# combo.net
KiCad netlist of a schematic drawn in EAGLE
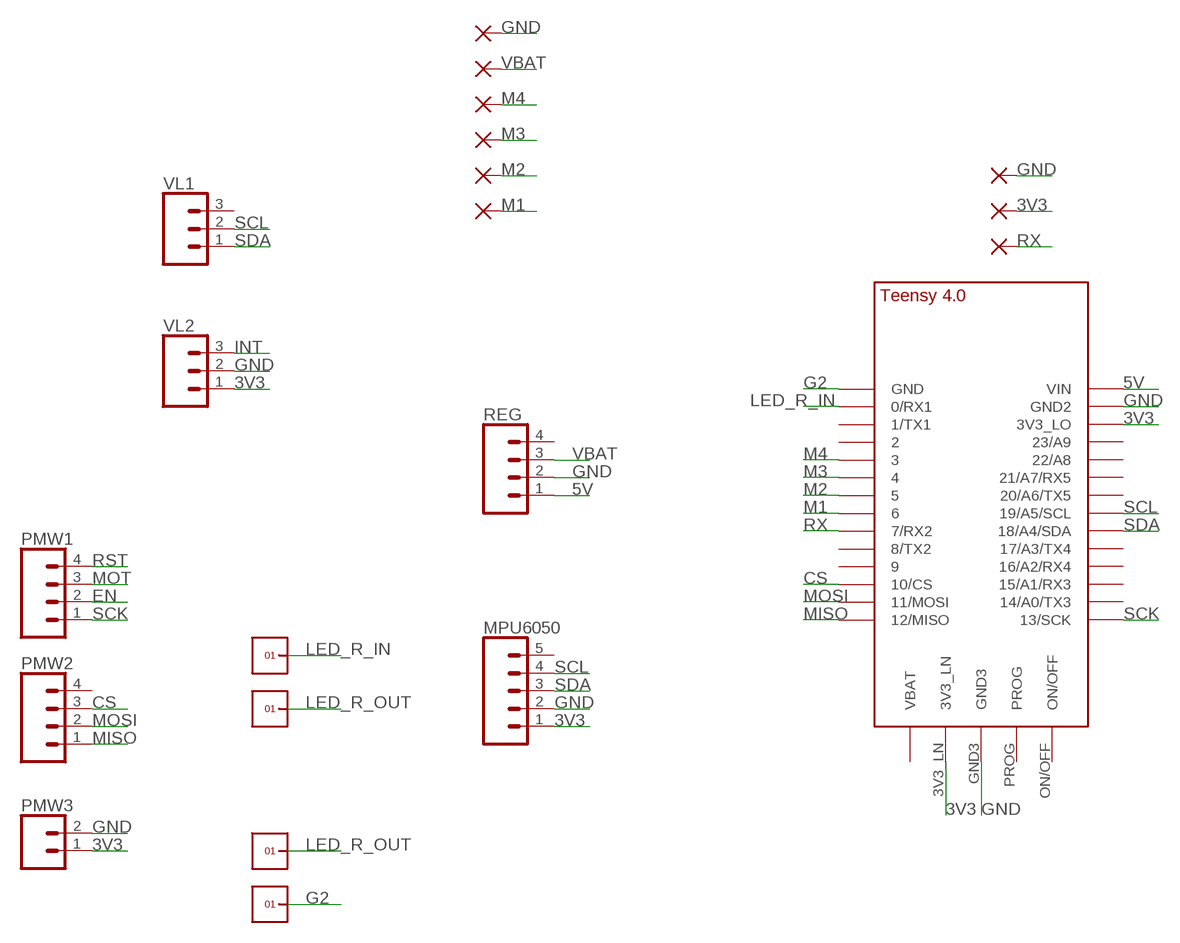
[diagram p0: schematic, sheet 1]

(export (version "E")
  (design (tool "Eeschema 10.0.6"))
  (components
    (comp (ref "3V")
      (value "SMD2")
      (footprint "eagle-import:SMD1,27-2,54")
      (libsource (lib "eagle-import") (part "SMD2"))
    )
    (comp (ref "GD")
      (value "SMD2")
      (footprint "eagle-import:SMD1,27-2,54")
      (libsource (lib "eagle-import") (part "SMD2"))
    )
    (comp (ref "GND")
      (value "SMD2")
      (footprint "eagle-import:SMD1,27-2,54")
      (libsource (lib "eagle-import") (part "SMD2"))
    )
    (comp (ref "M1")
      (value "SMD2")
      (footprint "eagle-import:SMD1,27-2,54")
      (libsource (lib "eagle-import") (part "SMD2"))
    )
    (comp (ref "M2")
      (value "SMD2")
      (footprint "eagle-import:SMD1,27-2,54")
      (libsource (lib "eagle-import") (part "SMD2"))
    )
    (comp (ref "M3")
      (value "SMD2")
      (footprint "eagle-import:SMD1,27-2,54")
      (libsource (lib "eagle-import") (part "SMD2"))
    )
    (comp (ref "M4")
      (value "SMD2")
      (footprint "eagle-import:SMD1,27-2,54")
      (libsource (lib "eagle-import") (part "SMD2"))
    )
    (comp (ref "MPU6050")
      (value "CONN_05NO_SILK")
      (footprint "eagle-import:1X05_NO_SILK")
      (libsource (lib "eagle-import") (part "CONN_05NO_SILK"))
    )
    (comp (ref "PMW1")
      (value "CONN_041X04_NO_SILK")
      (footprint "eagle-import:1X04_NO_SILK")
      (libsource (lib "eagle-import") (part "CONN_041X04_NO_SILK"))
    )
    (comp (ref "PMW2")
      (value "CONN_041X04_NO_SILK")
      (footprint "eagle-import:1X04_NO_SILK")
      (libsource (lib "eagle-import") (part "CONN_041X04_NO_SILK"))
    )
    (comp (ref "PMW3")
      (value "CONN_021X02_NO_SILK")
      (footprint "eagle-import:1X02_NO_SILK")
      (libsource (lib "eagle-import") (part "CONN_021X02_NO_SILK"))
    )
    (comp (ref "REG")
      (value "CONN_041X04_NO_SILK")
      (footprint "eagle-import:1X04_NO_SILK")
      (libsource (lib "eagle-import") (part "CONN_041X04_NO_SILK"))
    )
    (comp (ref "RX")
      (value "SMD2")
      (footprint "eagle-import:SMD1,27-2,54")
      (libsource (lib "eagle-import") (part "SMD2"))
    )
    (comp (ref "U$1")
      (value "TEENSY_4.0")
      (footprint "eagle-import:TEENSY_4.0")
      (libsource (lib "eagle-import") (part "TEENSY_4.0"))
    )
    (comp (ref "U$3")
      (value "1X1")
      (footprint "eagle-import:1X1")
      (libsource (lib "eagle-import") (part "1X1"))
    )
    (comp (ref "U$4")
      (value "1X1")
      (footprint "eagle-import:1X1")
      (libsource (lib "eagle-import") (part "1X1"))
    )
    (comp (ref "U$6")
      (value "1X1")
      (footprint "eagle-import:1X1")
      (libsource (lib "eagle-import") (part "1X1"))
    )
    (comp (ref "U$7")
      (value "1X1")
      (footprint "eagle-import:1X1")
      (libsource (lib "eagle-import") (part "1X1"))
    )
    (comp (ref "VBAT")
      (value "SMD2")
      (footprint "eagle-import:SMD1,27-2,54")
      (libsource (lib "eagle-import") (part "SMD2"))
    )
    (comp (ref "VL1")
      (value "CONN_031X03_NO_SILK")
      (footprint "eagle-import:1X03_NO_SILK")
      (libsource (lib "eagle-import") (part "CONN_031X03_NO_SILK"))
    )
    (comp (ref "VL2")
      (value "CONN_031X03_NO_SILK")
      (footprint "eagle-import:1X03_NO_SILK")
      (libsource (lib "eagle-import") (part "CONN_031X03_NO_SILK"))
    )
  )
  (nets
    (net (code "1") (name "/3V3") (class "Default")
      (node (ref "3V") (pin "1") (pinfunction "P_1") (pintype "passive"))
      (node (ref "MPU6050") (pin "1") (pinfunction "1_1") (pintype "passive"))
      (node (ref "PMW3") (pin "1") (pinfunction "1_1") (pintype "passive"))
      (node (ref "U$1") (pin "3V3_LN") (pinfunction "3V3_LN_3V3_LN") (pintype "bidirectional"))
      (node (ref "U$1") (pin "3V3_LO") (pinfunction "3V3_LO_3V3_LO") (pintype "bidirectional"))
      (node (ref "VL2") (pin "1") (pinfunction "1_1") (pintype "passive"))
    )
    (net (code "2") (name "/5V") (class "Default")
      (node (ref "REG") (pin "1") (pinfunction "1_1") (pintype "passive"))
      (node (ref "U$1") (pin "VIN") (pinfunction "VIN_VIN") (pintype "bidirectional"))
    )
    (net (code "3") (name "/CS") (class "Default")
      (node (ref "PMW2") (pin "3") (pinfunction "3_3") (pintype "passive"))
      (node (ref "U$1") (pin "10/CS") (pinfunction "10/CS_10/CS") (pintype "bidirectional"))
    )
    (net (code "4") (name "/EN") (class "Default")
      (node (ref "PMW1") (pin "2") (pinfunction "2_2") (pintype "passive"))
    )
    (net (code "5") (name "/G2") (class "Default")
      (node (ref "U$1") (pin "GND") (pinfunction "GND_GND") (pintype "bidirectional"))
      (node (ref "U$7") (pin "1") (pinfunction "1_1") (pintype "bidirectional"))
    )
    (net (code "6") (name "/GND") (class "Default")
      (node (ref "GD") (pin "1") (pinfunction "P_1") (pintype "passive"))
      (node (ref "GND") (pin "1") (pinfunction "P_1") (pintype "passive"))
      (node (ref "MPU6050") (pin "2") (pinfunction "2_2") (pintype "passive"))
      (node (ref "PMW3") (pin "2") (pinfunction "2_2") (pintype "passive"))
      (node (ref "REG") (pin "2") (pinfunction "2_2") (pintype "passive"))
      (node (ref "U$1") (pin "GND2") (pinfunction "GND2_GND2") (pintype "bidirectional"))
      (node (ref "U$1") (pin "GND3") (pinfunction "GND3_GND3") (pintype "bidirectional"))
      (node (ref "VL2") (pin "2") (pinfunction "2_2") (pintype "passive"))
    )
    (net (code "7") (name "/INT") (class "Default")
      (node (ref "VL2") (pin "3") (pinfunction "3_3") (pintype "passive"))
    )
    (net (code "8") (name "/LED_R_IN") (class "Default")
      (node (ref "U$1") (pin "0/RX") (pinfunction "0/RX1_0/RX") (pintype "bidirectional"))
      (node (ref "U$3") (pin "1") (pinfunction "1_1") (pintype "bidirectional"))
    )
    (net (code "9") (name "/LED_R_OUT") (class "Default")
      (node (ref "U$4") (pin "1") (pinfunction "1_1") (pintype "bidirectional"))
      (node (ref "U$6") (pin "1") (pinfunction "1_1") (pintype "bidirectional"))
    )
    (net (code "10") (name "/M1") (class "Default")
      (node (ref "M1") (pin "1") (pinfunction "P_1") (pintype "passive"))
      (node (ref "U$1") (pin "6") (pinfunction "6_6") (pintype "bidirectional"))
    )
    (net (code "11") (name "/M2") (class "Default")
      (node (ref "M2") (pin "1") (pinfunction "P_1") (pintype "passive"))
      (node (ref "U$1") (pin "5") (pinfunction "5_5") (pintype "bidirectional"))
    )
    (net (code "12") (name "/M3") (class "Default")
      (node (ref "M3") (pin "1") (pinfunction "P_1") (pintype "passive"))
      (node (ref "U$1") (pin "4/CANRX") (pinfunction "4_4/CANRX") (pintype "bidirectional"))
    )
    (net (code "13") (name "/M4") (class "Default")
      (node (ref "M4") (pin "1") (pinfunction "P_1") (pintype "passive"))
      (node (ref "U$1") (pin "3/CANTX") (pinfunction "3_3/CANTX") (pintype "bidirectional"))
    )
    (net (code "14") (name "/MISO") (class "Default")
      (node (ref "PMW2") (pin "1") (pinfunction "1_1") (pintype "passive"))
      (node (ref "U$1") (pin "12/MISO") (pinfunction "12/MISO_12/MISO") (pintype "bidirectional"))
    )
    (net (code "15") (name "/MOSI") (class "Default")
      (node (ref "PMW2") (pin "2") (pinfunction "2_2") (pintype "passive"))
      (node (ref "U$1") (pin "11/MOSI") (pinfunction "11/MOSI_11/MOSI") (pintype "bidirectional"))
    )
    (net (code "16") (name "/MOT") (class "Default")
      (node (ref "PMW1") (pin "3") (pinfunction "3_3") (pintype "passive"))
    )
    (net (code "17") (name "/RST") (class "Default")
      (node (ref "PMW1") (pin "4") (pinfunction "4_4") (pintype "passive"))
    )
    (net (code "18") (name "/RX") (class "Default")
      (node (ref "RX") (pin "1") (pinfunction "P_1") (pintype "passive"))
      (node (ref "U$1") (pin "7") (pinfunction "7/RX2_7") (pintype "bidirectional"))
    )
    (net (code "19") (name "/SCK") (class "Default")
      (node (ref "PMW1") (pin "1") (pinfunction "1_1") (pintype "passive"))
      (node (ref "U$1") (pin "13/SCK") (pinfunction "13/SCK_13/SCK") (pintype "bidirectional"))
    )
    (net (code "20") (name "/SCL") (class "Default")
      (node (ref "MPU6050") (pin "4") (pinfunction "4_4") (pintype "passive"))
      (node (ref "U$1") (pin "19/A5/SCL") (pinfunction "19/A5/SCL_19/A5/SCL") (pintype "bidirectional"))
      (node (ref "VL1") (pin "2") (pinfunction "2_2") (pintype "passive"))
    )
    (net (code "21") (name "/SDA") (class "Default")
      (node (ref "MPU6050") (pin "3") (pinfunction "3_3") (pintype "passive"))
      (node (ref "U$1") (pin "18/A4/SDA") (pinfunction "18/A4/SDA_18/A4/SDA") (pintype "bidirectional"))
      (node (ref "VL1") (pin "1") (pinfunction "1_1") (pintype "passive"))
    )
    (net (code "22") (name "/VBAT") (class "Default")
      (node (ref "REG") (pin "3") (pinfunction "3_3") (pintype "passive"))
      (node (ref "VBAT") (pin "1") (pinfunction "P_1") (pintype "passive"))
    )
    (net (code "23") (name "unconnected-(MPU6050-Pad5)") (class "Default")
      (node (ref "MPU6050") (pin "5") (pinfunction "5_5") (pintype "passive"))
    )
    (net (code "24") (name "unconnected-(PMW2-Pad4)") (class "Default")
      (node (ref "PMW2") (pin "4") (pinfunction "4_4") (pintype "passive"))
    )
    (net (code "25") (name "unconnected-(REG-Pad4)") (class "Default")
      (node (ref "REG") (pin "4") (pinfunction "4_4") (pintype "passive"))
    )
    (net (code "26") (name "unconnected-(U$1-1{slash}TX1-Pad1{slash}TX)") (class "Default")
      (node (ref "U$1") (pin "1/TX") (pinfunction "1/TX1_1/TX") (pintype "bidirectional"))
    )
    (net (code "27") (name "unconnected-(U$1-8{slash}TX2-Pad8)") (class "Default")
      (node (ref "U$1") (pin "8") (pinfunction "8/TX2_8") (pintype "bidirectional"))
    )
    (net (code "28") (name "unconnected-(U$1-9-Pad9{slash}CS)") (class "Default")
      (node (ref "U$1") (pin "9/CS") (pinfunction "9_9/CS") (pintype "bidirectional"))
    )
    (net (code "29") (name "unconnected-(U$1-14{slash}A0{slash}TX3-Pad14{slash}A0)") (class "Default")
      (node (ref "U$1") (pin "14/A0") (pinfunction "14/A0/TX3_14/A0") (pintype "bidirectional"))
    )
    (net (code "30") (name "unconnected-(U$1-15{slash}A1{slash}RX3-Pad15{slash}A1)") (class "Default")
      (node (ref "U$1") (pin "15/A1") (pinfunction "15/A1/RX3_15/A1") (pintype "bidirectional"))
    )
    (net (code "31") (name "unconnected-(U$1-16{slash}A2{slash}RX4-Pad16{slash}A2)") (class "Default")
      (node (ref "U$1") (pin "16/A2") (pinfunction "16/A2/RX4_16/A2") (pintype "bidirectional"))
    )
    (net (code "32") (name "unconnected-(U$1-17{slash}A3{slash}TX4-Pad17{slash}A3)") (class "Default")
      (node (ref "U$1") (pin "17/A3") (pinfunction "17/A3/TX4_17/A3") (pintype "bidirectional"))
    )
    (net (code "33") (name "unconnected-(U$1-20{slash}A6{slash}TX5-Pad20{slash}A6)") (class "Default")
      (node (ref "U$1") (pin "20/A6") (pinfunction "20/A6/TX5_20/A6") (pintype "bidirectional"))
    )
    (net (code "34") (name "unconnected-(U$1-21{slash}A7{slash}RX5-Pad21{slash}A7)") (class "Default")
      (node (ref "U$1") (pin "21/A7") (pinfunction "21/A7/RX5_21/A7") (pintype "bidirectional"))
    )
    (net (code "35") (name "unconnected-(U$1-Pad2)") (class "Default")
      (node (ref "U$1") (pin "2") (pinfunction "2_2") (pintype "bidirectional"))
    )
    (net (code "36") (name "unconnected-(U$1-Pad22{slash}A8)") (class "Default")
      (node (ref "U$1") (pin "22/A8") (pinfunction "22/A8_22/A8") (pintype "bidirectional"))
    )
    (net (code "37") (name "unconnected-(U$1-Pad23{slash}A9)") (class "Default")
      (node (ref "U$1") (pin "23/A9") (pinfunction "23/A9_23/A9") (pintype "bidirectional"))
    )
    (net (code "38") (name "unconnected-(U$1-PadON{slash}OFF)") (class "Default")
      (node (ref "U$1") (pin "ON/OFF") (pinfunction "ON/OFF_ON/OFF") (pintype "bidirectional"))
    )
    (net (code "39") (name "unconnected-(U$1-PadPROG)") (class "Default")
      (node (ref "U$1") (pin "PROG") (pinfunction "PROG_PROG") (pintype "bidirectional"))
    )
    (net (code "40") (name "unconnected-(U$1-VBAT-PadVBAT\\)") (class "Default")
      (node (ref "U$1") (pin "VBAT\\") (pinfunction "VBAT_VBAT\\") (pintype "bidirectional"))
    )
    (net (code "41") (name "unconnected-(VL1-Pad3)") (class "Default")
      (node (ref "VL1") (pin "3") (pinfunction "3_3") (pintype "passive"))
    )
  )
)
